# Relay_PCB.net
KiCad netlist of a schematic drawn in EAGLE
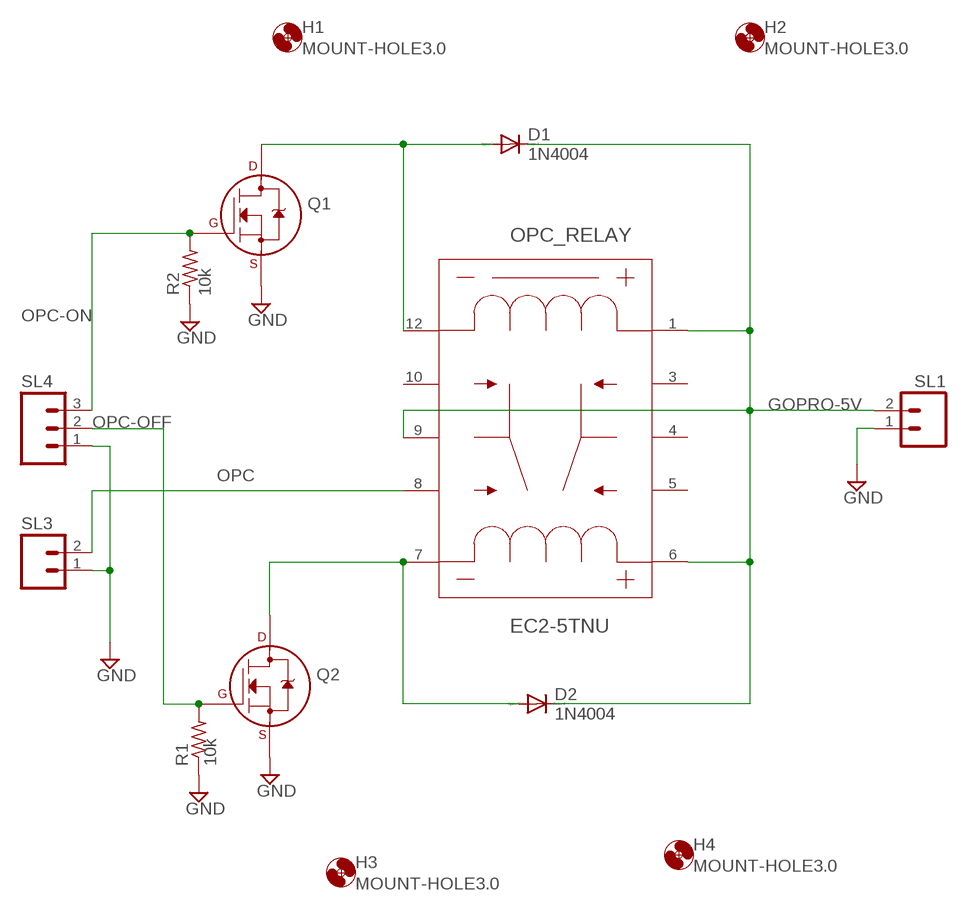
[diagram p0: schematic, sheet 1]

(export (version "E")
  (design (tool "Eeschema 10.0.6"))
  (components
    (comp (ref "D1")
      (value "1N4004")
      (footprint "eagle-import:DO41-10")
      (libsource (lib "eagle-import") (part "1N4004"))
    )
    (comp (ref "D2")
      (value "1N4004")
      (footprint "eagle-import:DO41-10")
      (libsource (lib "eagle-import") (part "1N4004"))
    )
    (comp (ref "H1")
      (value "MOUNT-HOLE3.0")
      (footprint "eagle-import:3,0")
      (libsource (lib "eagle-import") (part "MOUNT-HOLE3.0"))
    )
    (comp (ref "H2")
      (value "MOUNT-HOLE3.0")
      (footprint "eagle-import:3,0")
      (libsource (lib "eagle-import") (part "MOUNT-HOLE3.0"))
    )
    (comp (ref "H3")
      (value "MOUNT-HOLE3.0")
      (footprint "eagle-import:3,0")
      (libsource (lib "eagle-import") (part "MOUNT-HOLE3.0"))
    )
    (comp (ref "H4")
      (value "MOUNT-HOLE3.0")
      (footprint "eagle-import:3,0")
      (libsource (lib "eagle-import") (part "MOUNT-HOLE3.0"))
    )
    (comp (ref "OPC_RELAY")
      (value "EC2-5TNU")
      (footprint "eagle-import:EC2TNU")
      (fields (field (name "MANUFACTURER_PART_NUMBER") "EC25TNU"))
      (libsource (lib "eagle-import") (part "EC2-5TNU"))
    )
    (comp (ref "Q1")
      (value "2N7000_TO92")
      (footprint "eagle-import:TO-92")
      (libsource (lib "eagle-import") (part "2N700_TO920"))
    )
    (comp (ref "Q2")
      (value "2N7000_TO92")
      (footprint "eagle-import:TO-92")
      (libsource (lib "eagle-import") (part "2N700_TO920"))
    )
    (comp (ref "R1")
      (value "R-US_0207/7")
      (footprint "eagle-import:0207_7")
      (libsource (lib "eagle-import") (part "R-US_0207/7"))
    )
    (comp (ref "R2")
      (value "R-US_0207/7")
      (footprint "eagle-import:0207_7")
      (libsource (lib "eagle-import") (part "R-US_0207/7"))
    )
    (comp (ref "SL1")
      (value "M02")
      (footprint "eagle-import:02P")
      (libsource (lib "eagle-import") (part "M02"))
    )
    (comp (ref "SL3")
      (value "M02")
      (footprint "eagle-import:02P")
      (libsource (lib "eagle-import") (part "M02"))
    )
    (comp (ref "SL4")
      (value "M03")
      (footprint "eagle-import:03P")
      (libsource (lib "eagle-import") (part "M03"))
    )
  )
  (nets
    (net (code "1") (name "/GOPRO-5V") (class "Default")
      (node (ref "D1") (pin "C") (pinfunction "C_C") (pintype "passive"))
      (node (ref "D2") (pin "C") (pinfunction "C_C") (pintype "passive"))
      (node (ref "OPC_RELAY") (pin "1") (pinfunction "1_1") (pintype "passive"))
      (node (ref "OPC_RELAY") (pin "6") (pinfunction "5_6") (pintype "passive"))
      (node (ref "OPC_RELAY") (pin "9") (pinfunction "8_9") (pintype "passive"))
      (node (ref "SL1") (pin "2") (pinfunction "2_2") (pintype "passive"))
    )
    (net (code "2") (name "/OPC") (class "Default")
      (node (ref "OPC_RELAY") (pin "8") (pinfunction "7_8") (pintype "passive"))
      (node (ref "SL3") (pin "2") (pinfunction "2_2") (pintype "passive"))
    )
    (net (code "3") (name "/OPC-OFF") (class "Default")
      (node (ref "Q2") (pin "2") (pinfunction "G_2") (pintype "tri_state"))
      (node (ref "R1") (pin "2") (pinfunction "2_2") (pintype "passive"))
      (node (ref "SL4") (pin "2") (pinfunction "2_2") (pintype "passive"))
    )
    (net (code "4") (name "/OPC-ON") (class "Default")
      (node (ref "Q1") (pin "2") (pinfunction "G_2") (pintype "tri_state"))
      (node (ref "R2") (pin "2") (pinfunction "2_2") (pintype "passive"))
      (node (ref "SL4") (pin "3") (pinfunction "3_3") (pintype "passive"))
    )
    (net (code "5") (name "GND") (class "Default")
      (node (ref "Q1") (pin "1") (pinfunction "S_1") (pintype "bidirectional"))
      (node (ref "Q2") (pin "1") (pinfunction "S_1") (pintype "bidirectional"))
      (node (ref "R1") (pin "1") (pinfunction "1_1") (pintype "passive"))
      (node (ref "R2") (pin "1") (pinfunction "1_1") (pintype "passive"))
      (node (ref "SL1") (pin "1") (pinfunction "1_1") (pintype "passive"))
      (node (ref "SL3") (pin "1") (pinfunction "1_1") (pintype "passive"))
      (node (ref "SL4") (pin "1") (pinfunction "1_1") (pintype "passive"))
    )
    (net (code "6") (name "Net-(OPC_RELAY-6)") (class "Default")
      (node (ref "D2") (pin "A") (pinfunction "A_A") (pintype "passive"))
      (node (ref "OPC_RELAY") (pin "7") (pinfunction "6_7") (pintype "passive"))
      (node (ref "Q2") (pin "3") (pinfunction "D_3") (pintype "bidirectional"))
    )
    (net (code "7") (name "Net-(OPC_RELAY-10)") (class "Default")
      (node (ref "D1") (pin "A") (pinfunction "A_A") (pintype "passive"))
      (node (ref "OPC_RELAY") (pin "12") (pinfunction "10_12") (pintype "passive"))
      (node (ref "Q1") (pin "3") (pinfunction "D_3") (pintype "bidirectional"))
    )
    (net (code "8") (name "unconnected-(OPC_RELAY-2-Pad3)") (class "Default")
      (node (ref "OPC_RELAY") (pin "3") (pinfunction "2_3") (pintype "passive"))
    )
    (net (code "9") (name "unconnected-(OPC_RELAY-3-Pad4)") (class "Default")
      (node (ref "OPC_RELAY") (pin "4") (pinfunction "3_4") (pintype "passive"))
    )
    (net (code "10") (name "unconnected-(OPC_RELAY-4-Pad5)") (class "Default")
      (node (ref "OPC_RELAY") (pin "5") (pinfunction "4_5") (pintype "passive"))
    )
    (net (code "11") (name "unconnected-(OPC_RELAY-9-Pad10)") (class "Default")
      (node (ref "OPC_RELAY") (pin "10") (pinfunction "9_10") (pintype "passive"))
    )
  )
)
